# PCB-MicroBI16.net
KiCad netlist of a schematic drawn in EAGLE
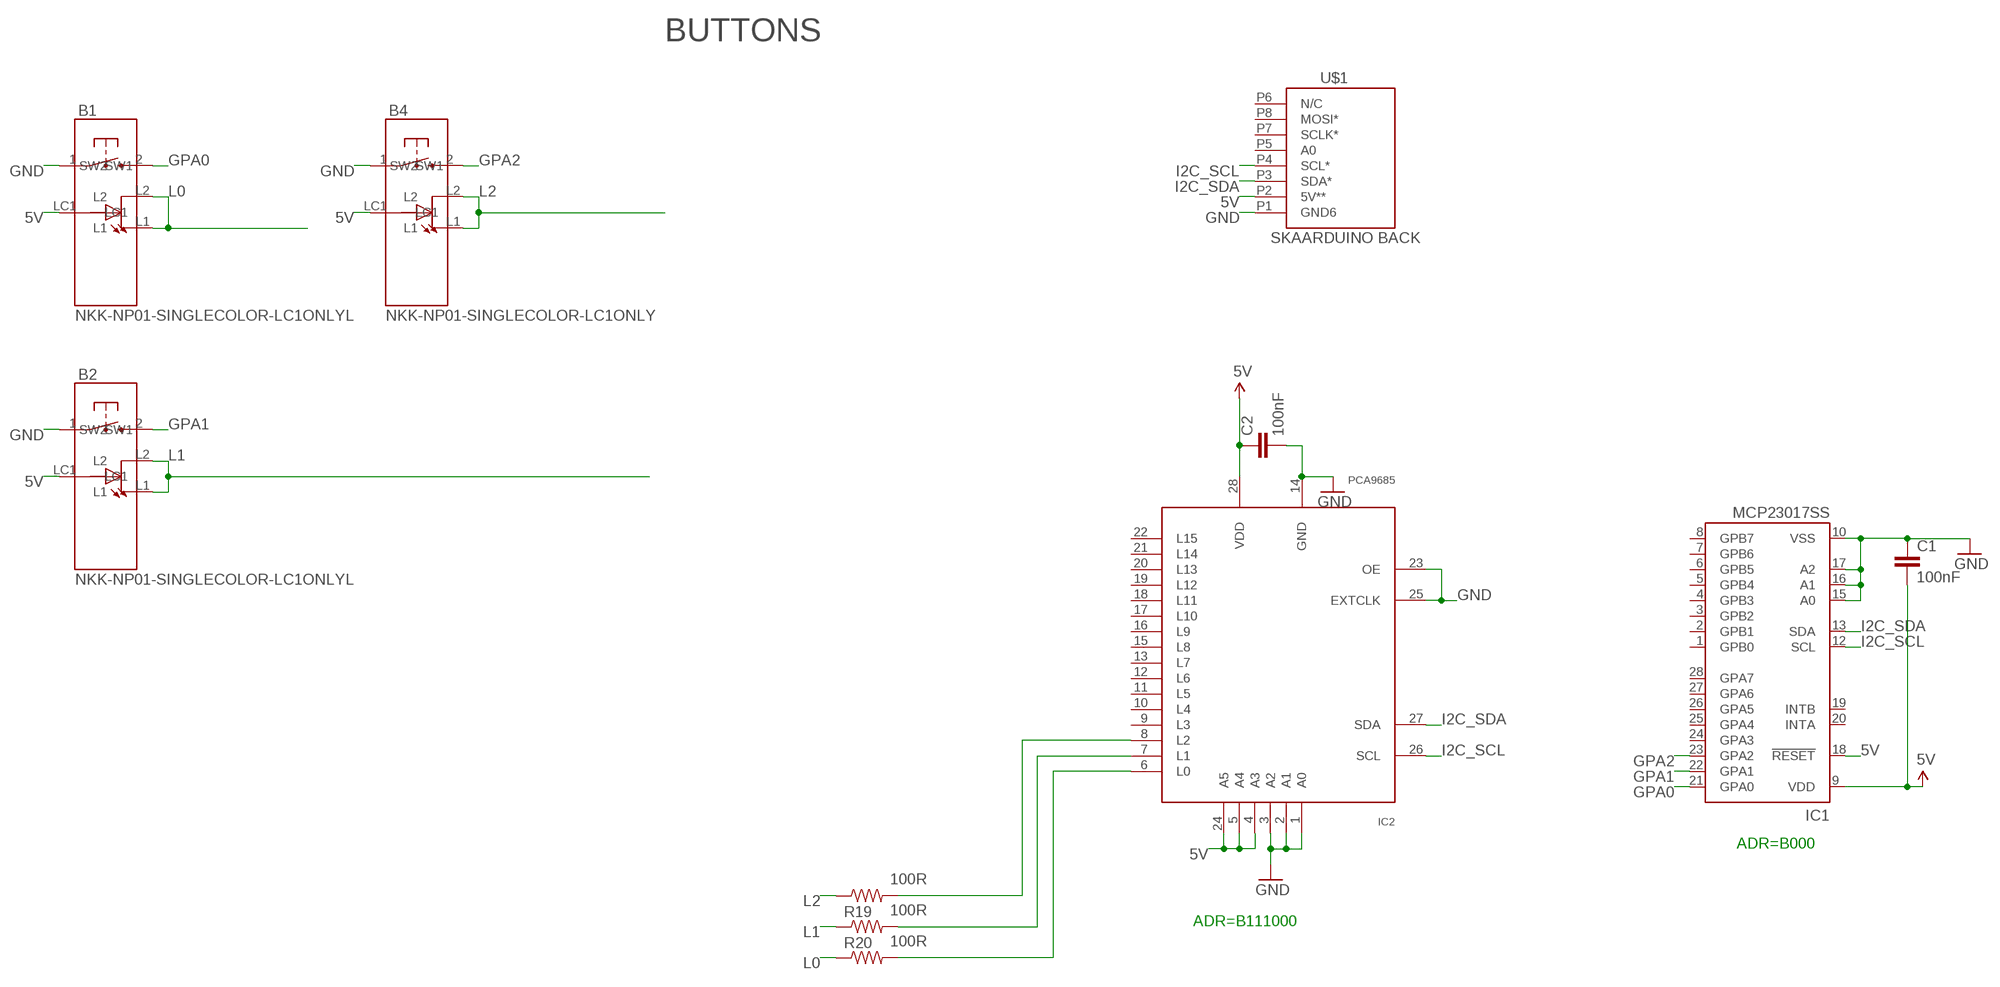
[diagram p0: schematic, sheet 1]

(export (version "E")
  (design (tool "Eeschema 10.0.6"))
  (components
    (comp (ref "B1")
      (value "NKK-NP01-SINGLECOLOR-LC1ONLYL")
      (footprint "eagle-import:NKK-NP01_LESSHOLES3")
      (libsource (lib "eagle-import") (part "NKK-NP01-SINGLECOLOR-LC1ONLYL"))
    )
    (comp (ref "B2")
      (value "NKK-NP01-SINGLECOLOR-LC1ONLYL")
      (footprint "eagle-import:NKK-NP01_LESSHOLES3")
      (libsource (lib "eagle-import") (part "NKK-NP01-SINGLECOLOR-LC1ONLYL"))
    )
    (comp (ref "B4")
      (value "NKK-NP01-SINGLECOLOR-LC1ONLY")
      (footprint "eagle-import:NKK-NP01_LESSHOLES2")
      (libsource (lib "eagle-import") (part "NKK-NP01-SINGLECOLOR-LC1ONLY"))
    )
    (comp (ref "C1")
      (value "100nF")
      (footprint "eagle-import:0603-CAP")
      (libsource (lib "eagle-import") (part "CAP0603-CAP"))
    )
    (comp (ref "C2")
      (value "100nF")
      (footprint "eagle-import:0603-CAP")
      (libsource (lib "eagle-import") (part "CAP0603-CAP"))
    )
    (comp (ref "IC1")
      (value "MCP23017SS")
      (footprint "eagle-import:SSOP28")
      (fields
        (field (name "MF") "MICROCHIP")
        (field (name "MPN") "MCP23017-E/SS")
        (field (name "MPN_1") "MCP23017-E/SS")
        (field (name "OC_FARNELL") "1467674")
        (field (name "OC_NEWARK") "31K2960")
      )
      (libsource (lib "eagle-import") (part "MCP23017SS"))
    )
    (comp (ref "IC2")
      (value "PCA9685")
      (footprint "eagle-import:TSSOP28")
      (libsource (lib "eagle-import") (part "PCA9685"))
    )
    (comp (ref "R18")
      (value "100R")
      (footprint "eagle-import:0603-RES")
      (libsource (lib "eagle-import") (part "RESISTOR0603-RES"))
    )
    (comp (ref "R19")
      (value "100R")
      (footprint "eagle-import:0603-RES")
      (libsource (lib "eagle-import") (part "RESISTOR0603-RES"))
    )
    (comp (ref "R20")
      (value "100R")
      (footprint "eagle-import:0603-RES")
      (libsource (lib "eagle-import") (part "RESISTOR0603-RES"))
    )
    (comp (ref "U$1")
      (value "SKAARDUINO_BACK_SERIAL")
      (footprint "eagle-import:SKAARDUINO_BACK_PTH_SERIAL")
      (libsource (lib "eagle-import") (part "SKAARDUINO_BACK_SERIAL"))
    )
  )
  (nets
    (net (code "1") (name "5V") (class "Default")
      (node (ref "B1") (pin "LC1") (pinfunction "LC1_LC1") (pintype "bidirectional"))
      (node (ref "B2") (pin "LC1") (pinfunction "LC1_LC1") (pintype "bidirectional"))
      (node (ref "B4") (pin "LC1") (pinfunction "LC1_LC1") (pintype "bidirectional"))
      (node (ref "C1") (pin "2") (pinfunction "2_2") (pintype "passive"))
      (node (ref "C2") (pin "1") (pinfunction "1_1") (pintype "passive"))
      (node (ref "IC1") (pin "18") (pinfunction "~{RESET}_18") (pintype "input"))
      (node (ref "IC1") (pin "9") (pinfunction "VDD_9") (pintype "power_in"))
      (node (ref "IC2") (pin "24") (pinfunction "A5_24") (pintype "input"))
      (node (ref "IC2") (pin "28") (pinfunction "VDD_28") (pintype "power_in"))
      (node (ref "IC2") (pin "4") (pinfunction "A3_4") (pintype "input"))
      (node (ref "IC2") (pin "5") (pinfunction "A4_5") (pintype "input"))
      (node (ref "U$1") (pin "P2") (pinfunction "5V**_P2") (pintype "power_in"))
    )
    (net (code "2") (name "GND") (class "Default")
      (node (ref "B1") (pin "1") (pinfunction "SW1_1") (pintype "bidirectional"))
      (node (ref "B2") (pin "1") (pinfunction "SW1_1") (pintype "bidirectional"))
      (node (ref "B4") (pin "1") (pinfunction "SW1_1") (pintype "bidirectional"))
      (node (ref "C1") (pin "1") (pinfunction "1_1") (pintype "passive"))
      (node (ref "C2") (pin "2") (pinfunction "2_2") (pintype "passive"))
      (node (ref "IC1") (pin "10") (pinfunction "VSS_10") (pintype "power_in"))
      (node (ref "IC1") (pin "15") (pinfunction "A0_15") (pintype "input"))
      (node (ref "IC1") (pin "16") (pinfunction "A1_16") (pintype "input"))
      (node (ref "IC1") (pin "17") (pinfunction "A2_17") (pintype "input"))
      (node (ref "IC2") (pin "1") (pinfunction "A0_1") (pintype "input"))
      (node (ref "IC2") (pin "14") (pinfunction "GND_14") (pintype "power_in"))
      (node (ref "IC2") (pin "2") (pinfunction "A1_2") (pintype "input"))
      (node (ref "IC2") (pin "23") (pinfunction "OE_23") (pintype "input"))
      (node (ref "IC2") (pin "25") (pinfunction "EXTCLK_25") (pintype "input"))
      (node (ref "IC2") (pin "3") (pinfunction "A2_3") (pintype "input"))
      (node (ref "U$1") (pin "P1") (pinfunction "GND6_P1") (pintype "power_in"))
    )
    (net (code "3") (name "GPA0") (class "Default")
      (node (ref "B1") (pin "2") (pinfunction "SW2_2") (pintype "bidirectional"))
      (node (ref "IC1") (pin "21") (pinfunction "GPA0_21") (pintype "bidirectional"))
    )
    (net (code "4") (name "GPA1") (class "Default")
      (node (ref "B2") (pin "2") (pinfunction "SW2_2") (pintype "bidirectional"))
      (node (ref "IC1") (pin "22") (pinfunction "GPA1_22") (pintype "bidirectional"))
    )
    (net (code "5") (name "GPA2") (class "Default")
      (node (ref "B4") (pin "2") (pinfunction "SW2_2") (pintype "bidirectional"))
      (node (ref "IC1") (pin "23") (pinfunction "GPA2_23") (pintype "bidirectional"))
    )
    (net (code "6") (name "I2C_SCL") (class "Default")
      (node (ref "IC1") (pin "12") (pinfunction "SCL_12") (pintype "input"))
      (node (ref "IC2") (pin "26") (pinfunction "SCL_26") (pintype "input"))
      (node (ref "U$1") (pin "P4") (pinfunction "SCL*_P4") (pintype "bidirectional"))
    )
    (net (code "7") (name "I2C_SDA") (class "Default")
      (node (ref "IC1") (pin "13") (pinfunction "SDA_13") (pintype "bidirectional"))
      (node (ref "IC2") (pin "27") (pinfunction "SDA_27") (pintype "input"))
      (node (ref "U$1") (pin "P3") (pinfunction "SDA*_P3") (pintype "bidirectional"))
    )
    (net (code "8") (name "L0") (class "Default")
      (node (ref "B1") (pin "L1") (pinfunction "L1_L1") (pintype "bidirectional"))
      (node (ref "B1") (pin "L2") (pinfunction "L2_L2") (pintype "bidirectional"))
      (node (ref "R20") (pin "1") (pinfunction "1_1") (pintype "passive"))
    )
    (net (code "9") (name "L1") (class "Default")
      (node (ref "B2") (pin "L1") (pinfunction "L1_L1") (pintype "bidirectional"))
      (node (ref "B2") (pin "L2") (pinfunction "L2_L2") (pintype "bidirectional"))
      (node (ref "R19") (pin "1") (pinfunction "1_1") (pintype "passive"))
    )
    (net (code "10") (name "L2") (class "Default")
      (node (ref "B4") (pin "L1") (pinfunction "L1_L1") (pintype "bidirectional"))
      (node (ref "B4") (pin "L2") (pinfunction "L2_L2") (pintype "bidirectional"))
      (node (ref "R18") (pin "1") (pinfunction "1_1") (pintype "passive"))
    )
    (net (code "11") (name "Net-(IC2-L0)") (class "Default")
      (node (ref "IC2") (pin "6") (pinfunction "L0_6") (pintype "output"))
      (node (ref "R20") (pin "2") (pinfunction "2_2") (pintype "passive"))
    )
    (net (code "12") (name "Net-(IC2-L1)") (class "Default")
      (node (ref "IC2") (pin "7") (pinfunction "L1_7") (pintype "output"))
      (node (ref "R19") (pin "2") (pinfunction "2_2") (pintype "passive"))
    )
    (net (code "13") (name "Net-(IC2-L2)") (class "Default")
      (node (ref "IC2") (pin "8") (pinfunction "L2_8") (pintype "output"))
      (node (ref "R18") (pin "2") (pinfunction "2_2") (pintype "passive"))
    )
    (net (code "14") (name "unconnected-(IC1-GPA3-Pad24)") (class "Default")
      (node (ref "IC1") (pin "24") (pinfunction "GPA3_24") (pintype "bidirectional"))
    )
    (net (code "15") (name "unconnected-(IC1-GPA4-Pad25)") (class "Default")
      (node (ref "IC1") (pin "25") (pinfunction "GPA4_25") (pintype "bidirectional"))
    )
    (net (code "16") (name "unconnected-(IC1-GPA5-Pad26)") (class "Default")
      (node (ref "IC1") (pin "26") (pinfunction "GPA5_26") (pintype "bidirectional"))
    )
    (net (code "17") (name "unconnected-(IC1-GPA6-Pad27)") (class "Default")
      (node (ref "IC1") (pin "27") (pinfunction "GPA6_27") (pintype "bidirectional"))
    )
    (net (code "18") (name "unconnected-(IC1-GPA7-Pad28)") (class "Default")
      (node (ref "IC1") (pin "28") (pinfunction "GPA7_28") (pintype "bidirectional"))
    )
    (net (code "19") (name "unconnected-(IC1-GPB0-Pad1)") (class "Default")
      (node (ref "IC1") (pin "1") (pinfunction "GPB0_1") (pintype "bidirectional"))
    )
    (net (code "20") (name "unconnected-(IC1-GPB1-Pad2)") (class "Default")
      (node (ref "IC1") (pin "2") (pinfunction "GPB1_2") (pintype "bidirectional"))
    )
    (net (code "21") (name "unconnected-(IC1-GPB2-Pad3)") (class "Default")
      (node (ref "IC1") (pin "3") (pinfunction "GPB2_3") (pintype "bidirectional"))
    )
    (net (code "22") (name "unconnected-(IC1-GPB3-Pad4)") (class "Default")
      (node (ref "IC1") (pin "4") (pinfunction "GPB3_4") (pintype "bidirectional"))
    )
    (net (code "23") (name "unconnected-(IC1-GPB4-Pad5)") (class "Default")
      (node (ref "IC1") (pin "5") (pinfunction "GPB4_5") (pintype "bidirectional"))
    )
    (net (code "24") (name "unconnected-(IC1-GPB5-Pad6)") (class "Default")
      (node (ref "IC1") (pin "6") (pinfunction "GPB5_6") (pintype "bidirectional"))
    )
    (net (code "25") (name "unconnected-(IC1-GPB6-Pad7)") (class "Default")
      (node (ref "IC1") (pin "7") (pinfunction "GPB6_7") (pintype "bidirectional"))
    )
    (net (code "26") (name "unconnected-(IC1-GPB7-Pad8)") (class "Default")
      (node (ref "IC1") (pin "8") (pinfunction "GPB7_8") (pintype "bidirectional"))
    )
    (net (code "27") (name "unconnected-(IC1-INTA-Pad20)") (class "Default")
      (node (ref "IC1") (pin "20") (pinfunction "INTA_20") (pintype "output"))
    )
    (net (code "28") (name "unconnected-(IC1-INTB-Pad19)") (class "Default")
      (node (ref "IC1") (pin "19") (pinfunction "INTB_19") (pintype "output"))
    )
    (net (code "29") (name "unconnected-(IC2-L3-Pad9)") (class "Default")
      (node (ref "IC2") (pin "9") (pinfunction "L3_9") (pintype "output"))
    )
    (net (code "30") (name "unconnected-(IC2-L4-Pad10)") (class "Default")
      (node (ref "IC2") (pin "10") (pinfunction "L4_10") (pintype "output"))
    )
    (net (code "31") (name "unconnected-(IC2-L5-Pad11)") (class "Default")
      (node (ref "IC2") (pin "11") (pinfunction "L5_11") (pintype "output"))
    )
    (net (code "32") (name "unconnected-(IC2-L6-Pad12)") (class "Default")
      (node (ref "IC2") (pin "12") (pinfunction "L6_12") (pintype "output"))
    )
    (net (code "33") (name "unconnected-(IC2-L7-Pad13)") (class "Default")
      (node (ref "IC2") (pin "13") (pinfunction "L7_13") (pintype "output"))
    )
    (net (code "34") (name "unconnected-(IC2-L8-Pad15)") (class "Default")
      (node (ref "IC2") (pin "15") (pinfunction "L8_15") (pintype "output"))
    )
    (net (code "35") (name "unconnected-(IC2-L9-Pad16)") (class "Default")
      (node (ref "IC2") (pin "16") (pinfunction "L9_16") (pintype "output"))
    )
    (net (code "36") (name "unconnected-(IC2-L10-Pad17)") (class "Default")
      (node (ref "IC2") (pin "17") (pinfunction "L10_17") (pintype "output"))
    )
    (net (code "37") (name "unconnected-(IC2-L11-Pad18)") (class "Default")
      (node (ref "IC2") (pin "18") (pinfunction "L11_18") (pintype "output"))
    )
    (net (code "38") (name "unconnected-(IC2-L12-Pad19)") (class "Default")
      (node (ref "IC2") (pin "19") (pinfunction "L12_19") (pintype "output"))
    )
    (net (code "39") (name "unconnected-(IC2-L13-Pad20)") (class "Default")
      (node (ref "IC2") (pin "20") (pinfunction "L13_20") (pintype "output"))
    )
    (net (code "40") (name "unconnected-(IC2-L14-Pad21)") (class "Default")
      (node (ref "IC2") (pin "21") (pinfunction "L14_21") (pintype "output"))
    )
    (net (code "41") (name "unconnected-(IC2-L15-Pad22)") (class "Default")
      (node (ref "IC2") (pin "22") (pinfunction "L15_22") (pintype "output"))
    )
    (net (code "42") (name "unconnected-(U$1-A0-PadP5)") (class "Default")
      (node (ref "U$1") (pin "P5") (pinfunction "A0_P5") (pintype "bidirectional"))
    )
    (net (code "43") (name "unconnected-(U$1-MOSI*-PadP8)") (class "Default")
      (node (ref "U$1") (pin "P8") (pinfunction "MOSI*_P8") (pintype "output"))
    )
    (net (code "44") (name "unconnected-(U$1-N{slash}C-PadP6)") (class "Default")
      (node (ref "U$1") (pin "P6") (pinfunction "N/C_P6") (pintype "bidirectional"))
    )
    (net (code "45") (name "unconnected-(U$1-SCLK*-PadP7)") (class "Default")
      (node (ref "U$1") (pin "P7") (pinfunction "SCLK*_P7") (pintype "output"))
    )
  )
)
